# DAC_Amplifier.net
KiCad netlist of a schematic drawn in Altium Designer
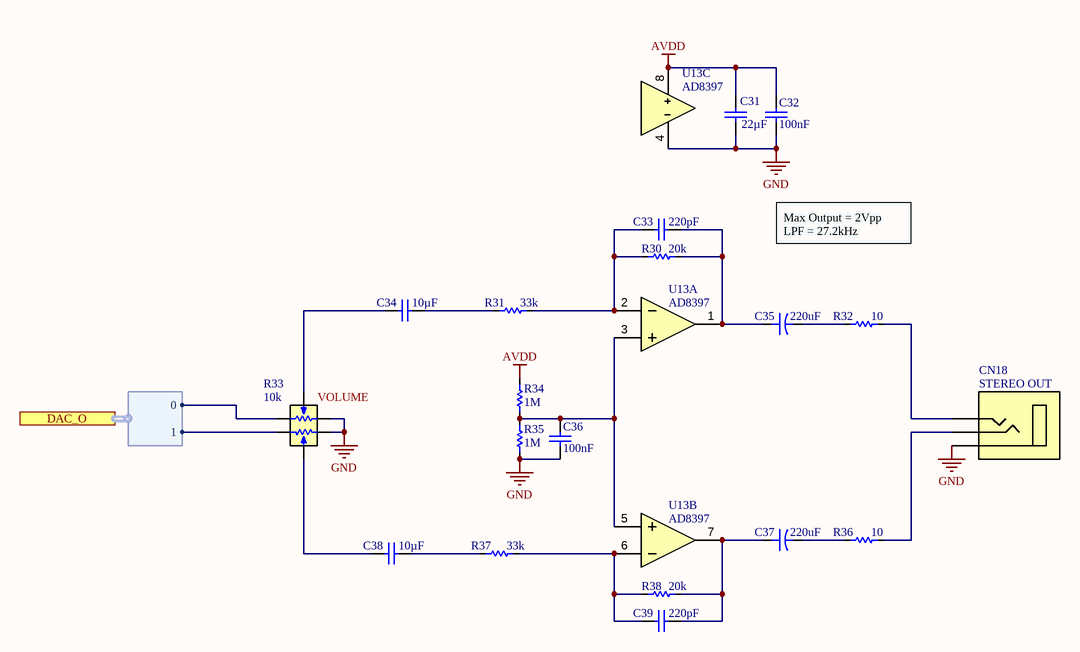
[diagram p0: DAC Amplifier.SchDoc]

(export (version "E")
  (design (tool "Eeschema 10.0.6"))
  (components
    (comp (ref "C31")
      (value "22µF")
      (footprint "CAP_CHIP_0805")
      (description "0805 Multilayer Ceramic Capacitors MLCC")
      (fields (field (name "TOLERANCE") "20%") (field (name "PARTNUMBER") "CL21A226MAQNNNE"))
      (libsource (lib "Sainsbury Wellcome Centre") (part "Cap"))
    )
    (comp (ref "C32")
      (value "100nF")
      (footprint "CAP_CHIP_0603")
      (description "0603 Multilayer Ceramic Capacitors MLCC")
      (fields (field (name "PARTNUMBER") "CC0603KRX7R9BB104") (field (name "TOLERANCE") "10%"))
      (libsource (lib "Sainsbury Wellcome Centre") (part "Cap"))
    )
    (comp (ref "C33")
      (value "220pF")
      (footprint "CAP_CHIP_0603")
      (description "0603 Multilayer Ceramic Capacitors MLCC")
      (fields (field (name "PARTNUMBER") "CL10B221KB8NNNC") (field (name "TOLERANCE") "10%"))
      (libsource (lib "Sainsbury Wellcome Centre") (part "Cap"))
    )
    (comp (ref "C34")
      (value "10µF")
      (footprint "CAP_CHIP_0603")
      (description "0603 Multilayer Ceramic Capacitors MLCC")
      (fields (field (name "PARTNUMBER") "CL10A106MA8NRNC") (field (name "TOLERANCE") "20%"))
      (libsource (lib "Sainsbury Wellcome Centre") (part "Cap"))
    )
    (comp (ref "C35")
      (value "220uF")
      (footprint "ECAP_SMD_6.3X5.4")
      (description "10µF ±20% 50V SMD Aluminum Electrolytic Capacitor Surface Mount D")
      (fields (field (name "TOLERANCE") "20%") (field (name "PARTNUMBER") "CK1A221M-CRE54"))
      (libsource (lib "Sainsbury Wellcome Centre") (part "Cap Pol 2"))
    )
    (comp (ref "C36")
      (value "100nF")
      (footprint "CAP_CHIP_0603")
      (description "0603 Multilayer Ceramic Capacitors MLCC")
      (fields (field (name "PARTNUMBER") "CC0603KRX7R9BB104") (field (name "TOLERANCE") "10%"))
      (libsource (lib "Sainsbury Wellcome Centre") (part "Cap"))
    )
    (comp (ref "C37")
      (value "220uF")
      (footprint "ECAP_SMD_6.3X5.4")
      (description "10µF ±20% 50V SMD Aluminum Electrolytic Capacitor Surface Mount D")
      (fields (field (name "TOLERANCE") "20%") (field (name "PARTNUMBER") "CK1A221M-CRE54"))
      (libsource (lib "Sainsbury Wellcome Centre") (part "Cap Pol 2"))
    )
    (comp (ref "C38")
      (value "10µF")
      (footprint "CAP_CHIP_0603")
      (description "0603 Multilayer Ceramic Capacitors MLCC")
      (fields (field (name "PARTNUMBER") "CL10A106MA8NRNC") (field (name "TOLERANCE") "20%"))
      (libsource (lib "Sainsbury Wellcome Centre") (part "Cap"))
    )
    (comp (ref "C39")
      (value "220pF")
      (footprint "CAP_CHIP_0603")
      (description "0603 Multilayer Ceramic Capacitors MLCC")
      (fields (field (name "PARTNUMBER") "CL10B221KB8NNNC") (field (name "TOLERANCE") "10%"))
      (libsource (lib "Sainsbury Wellcome Centre") (part "Cap"))
    )
    (comp (ref "CN18")
      (value "STEREO OUT")
      (footprint "PJ-3920")
      (description "3.5mm Headphone Jack 30V 500mA Plugin Audio Connectors")
      (fields (field (name "PARTNUMBER") "PJ-3920-3A"))
      (libsource (lib "Sainsbury Wellcome Centre") (part "PJ-3920"))
    )
    (comp (ref "R30")
      (value "20k")
      (footprint "RES_CHIP_0603")
      (description "100mW Thick Film Resistors 75V ±100ppm/℃ ±1% 0603 Chip Resistor")
      (fields (field (name "TOLERANCE") "1%") (field (name "PARTNUMBER") "0603WAF2002T5E"))
      (libsource (lib "Sainsbury Wellcome Centre") (part "Res"))
    )
    (comp (ref "R31")
      (value "33k")
      (footprint "RES_CHIP_0603")
      (description "100mW Thick Film Resistors 75V ±100ppm/℃ ±1% 0603 Chip Resistor")
      (fields (field (name "TOLERANCE") "1%") (field (name "PARTNUMBER") "0603WAF3302T5E"))
      (libsource (lib "Sainsbury Wellcome Centre") (part "Res"))
    )
    (comp (ref "R32")
      (value "10")
      (footprint "RES_CHIP_1206")
      (description "Res Thick Film 1206 10 Ohm 5% 0.75W(3/4W) ±200ppm/C Pad SMD Automotive T/R")
      (fields (field (name "TOLERANCE") "5%") (field (name "PARTNUMBER") "CRCW120610R0JNEAHP"))
      (libsource (lib "Sainsbury Wellcome Centre") (part "Res"))
    )
    (comp (ref "R33")
      (value "VOLUME")
      (footprint "VR_RK12L12C")
      (description "Res POT 10K Ohm 20% 1(Elec)/1(Mech)Turns 6mm (13 X 28.5mm) Snap-In Panel Mount")
      (fields
        (field (name "ALTIUM_VALUE") "10k")
        (field (name "PARTNUMBER") "RK12L12C0A0E")
        (field (name "TOLERANCE") "20%")
      )
      (libsource (lib "Sainsbury Wellcome Centre") (part "Pot Dual"))
    )
    (comp (ref "R34")
      (value "1M")
      (footprint "RES_CHIP_0603")
      (description "100mW Thick Film Resistors 75V ±100ppm/℃ ±1% 0603 Chip Resistor")
      (fields (field (name "PARTNUMBER") "0603WAF1004T5E") (field (name "TOLERANCE") "1%"))
      (libsource (lib "Sainsbury Wellcome Centre") (part "Res"))
    )
    (comp (ref "R35")
      (value "1M")
      (footprint "RES_CHIP_0603")
      (description "100mW Thick Film Resistors 75V ±100ppm/℃ ±1% 0603 Chip Resistor")
      (fields (field (name "PARTNUMBER") "0603WAF1004T5E") (field (name "TOLERANCE") "1%"))
      (libsource (lib "Sainsbury Wellcome Centre") (part "Res"))
    )
    (comp (ref "R36")
      (value "10")
      (footprint "RES_CHIP_1206")
      (description "Res Thick Film 1206 10 Ohm 5% 0.75W(3/4W) ±200ppm/C Pad SMD Automotive T/R")
      (fields (field (name "TOLERANCE") "5%") (field (name "PARTNUMBER") "CRCW120610R0JNEAHP"))
      (libsource (lib "Sainsbury Wellcome Centre") (part "Res"))
    )
    (comp (ref "R37")
      (value "33k")
      (footprint "RES_CHIP_0603")
      (description "100mW Thick Film Resistors 75V ±100ppm/℃ ±1% 0603 Chip Resistor")
      (fields (field (name "TOLERANCE") "1%") (field (name "PARTNUMBER") "0603WAF3302T5E"))
      (libsource (lib "Sainsbury Wellcome Centre") (part "Res"))
    )
    (comp (ref "R38")
      (value "20k")
      (footprint "RES_CHIP_0603")
      (description "100mW Thick Film Resistors 75V ±100ppm/℃ ±1% 0603 Chip Resistor")
      (fields (field (name "TOLERANCE") "1%") (field (name "PARTNUMBER") "0603WAF2002T5E"))
      (libsource (lib "Sainsbury Wellcome Centre") (part "Res"))
    )
    (comp (ref "U13")
      (value "AD8397")
      (footprint "SOIC8_AD8397")
      (description "Op Amp Dual High Output Current Amplifier R-R O/P ±12.6V/25.2V 8-Pin SOIC N EP Tube")
      (fields (field (name "PARTNUMBER") "AD8397ARDZ"))
      (libsource (lib "Sainsbury Wellcome Centre") (part "OPAMP 8P"))
    )
  )
  (nets
    (net (code "2") (name "/0") (class "Default")
      (node (ref "R33") (pin "2") (pinfunction "BOT_A_2") (pintype "passive"))
    )
    (net (code "3") (name "/1") (class "Default")
      (node (ref "R33") (pin "5") (pinfunction "BOT_B_5") (pintype "passive"))
    )
    (net (code "5") (name "AVDD") (class "Default")
      (node (ref "C31") (pin "2") (pinfunction "2_2") (pintype "passive"))
      (node (ref "C32") (pin "2") (pinfunction "2_2") (pintype "passive"))
      (node (ref "R34") (pin "2") (pinfunction "2_2") (pintype "passive"))
      (node (ref "U13") (pin "8") (pinfunction "V+_8") (pintype "power_in"))
    )
    (net (code "6") (name "GND") (class "Default")
      (node (ref "C31") (pin "1") (pinfunction "1_1") (pintype "passive"))
      (node (ref "C32") (pin "1") (pinfunction "1_1") (pintype "passive"))
      (node (ref "C36") (pin "1") (pinfunction "1_1") (pintype "passive"))
      (node (ref "CN18") (pin "1") (pinfunction "S_1") (pintype "passive"))
      (node (ref "R33") (pin "1") (pinfunction "TOP_A_1") (pintype "passive"))
      (node (ref "R33") (pin "4") (pinfunction "TOP_B_4") (pintype "passive"))
      (node (ref "R35") (pin "1") (pinfunction "1_1") (pintype "passive"))
      (node (ref "U13") (pin "4") (pinfunction "V-_4") (pintype "power_in"))
    )
    (net (code "7") (name "Net-(C34-Pad2)") (class "Default")
      (node (ref "C34") (pin "2") (pinfunction "2_2") (pintype "passive"))
      (node (ref "R31") (pin "1") (pinfunction "1_1") (pintype "passive"))
    )
    (net (code "8") (name "Net-(C35-Pad2)") (class "Default")
      (node (ref "C35") (pin "2") (pinfunction "2_2") (pintype "passive"))
      (node (ref "R32") (pin "1") (pinfunction "1_1") (pintype "passive"))
    )
    (net (code "9") (name "Net-(C37-Pad2)") (class "Default")
      (node (ref "C37") (pin "2") (pinfunction "2_2") (pintype "passive"))
      (node (ref "R36") (pin "1") (pinfunction "1_1") (pintype "passive"))
    )
    (net (code "10") (name "Net-(C38-Pad2)") (class "Default")
      (node (ref "C38") (pin "2") (pinfunction "2_2") (pintype "passive"))
      (node (ref "R37") (pin "1") (pinfunction "1_1") (pintype "passive"))
    )
    (net (code "11") (name "Net-(CN18-R)") (class "Default")
      (node (ref "CN18") (pin "3") (pinfunction "R_3") (pintype "passive"))
      (node (ref "R36") (pin "2") (pinfunction "2_2") (pintype "passive"))
    )
    (net (code "12") (name "Net-(CN18-T)") (class "Default")
      (node (ref "CN18") (pin "2") (pinfunction "T_2") (pintype "passive"))
      (node (ref "R32") (pin "2") (pinfunction "2_2") (pintype "passive"))
    )
    (net (code "13") (name "Net-(R33-TAP_A)") (class "Default")
      (node (ref "C34") (pin "1") (pinfunction "1_1") (pintype "passive"))
      (node (ref "R33") (pin "3") (pinfunction "TAP_A_3") (pintype "passive"))
    )
    (net (code "14") (name "Net-(R33-TAP_B)") (class "Default")
      (node (ref "C38") (pin "1") (pinfunction "1_1") (pintype "passive"))
      (node (ref "R33") (pin "6") (pinfunction "TAP_B_6") (pintype "passive"))
    )
    (net (code "15") (name "Net-(U13A-A+)") (class "Default")
      (node (ref "C36") (pin "2") (pinfunction "2_2") (pintype "passive"))
      (node (ref "R34") (pin "1") (pinfunction "1_1") (pintype "passive"))
      (node (ref "R35") (pin "2") (pinfunction "2_2") (pintype "passive"))
      (node (ref "U13") (pin "3") (pinfunction "A+_3") (pintype "passive"))
      (node (ref "U13") (pin "5") (pinfunction "B+_5") (pintype "passive"))
    )
    (net (code "16") (name "Net-(U13A-A-)") (class "Default")
      (node (ref "C33") (pin "1") (pinfunction "1_1") (pintype "passive"))
      (node (ref "R30") (pin "1") (pinfunction "1_1") (pintype "passive"))
      (node (ref "R31") (pin "2") (pinfunction "2_2") (pintype "passive"))
      (node (ref "U13") (pin "2") (pinfunction "A-_2") (pintype "passive"))
    )
    (net (code "17") (name "Net-(U13A-AOUT)") (class "Default")
      (node (ref "C33") (pin "2") (pinfunction "2_2") (pintype "passive"))
      (node (ref "C35") (pin "1") (pinfunction "1_1") (pintype "passive"))
      (node (ref "R30") (pin "2") (pinfunction "2_2") (pintype "passive"))
      (node (ref "U13") (pin "1") (pinfunction "AOUT_1") (pintype "passive"))
    )
    (net (code "18") (name "Net-(U13B-B-)") (class "Default")
      (node (ref "C39") (pin "1") (pinfunction "1_1") (pintype "passive"))
      (node (ref "R37") (pin "2") (pinfunction "2_2") (pintype "passive"))
      (node (ref "R38") (pin "1") (pinfunction "1_1") (pintype "passive"))
      (node (ref "U13") (pin "6") (pinfunction "B-_6") (pintype "passive"))
    )
    (net (code "19") (name "Net-(U13B-BOUT)") (class "Default")
      (node (ref "C37") (pin "1") (pinfunction "1_1") (pintype "passive"))
      (node (ref "C39") (pin "2") (pinfunction "2_2") (pintype "passive"))
      (node (ref "R38") (pin "2") (pinfunction "2_2") (pintype "passive"))
      (node (ref "U13") (pin "7") (pinfunction "BOUT_7") (pintype "passive"))
    )
  )
)
